# connectors.net
KiCad netlist of a schematic drawn in Altium Designer
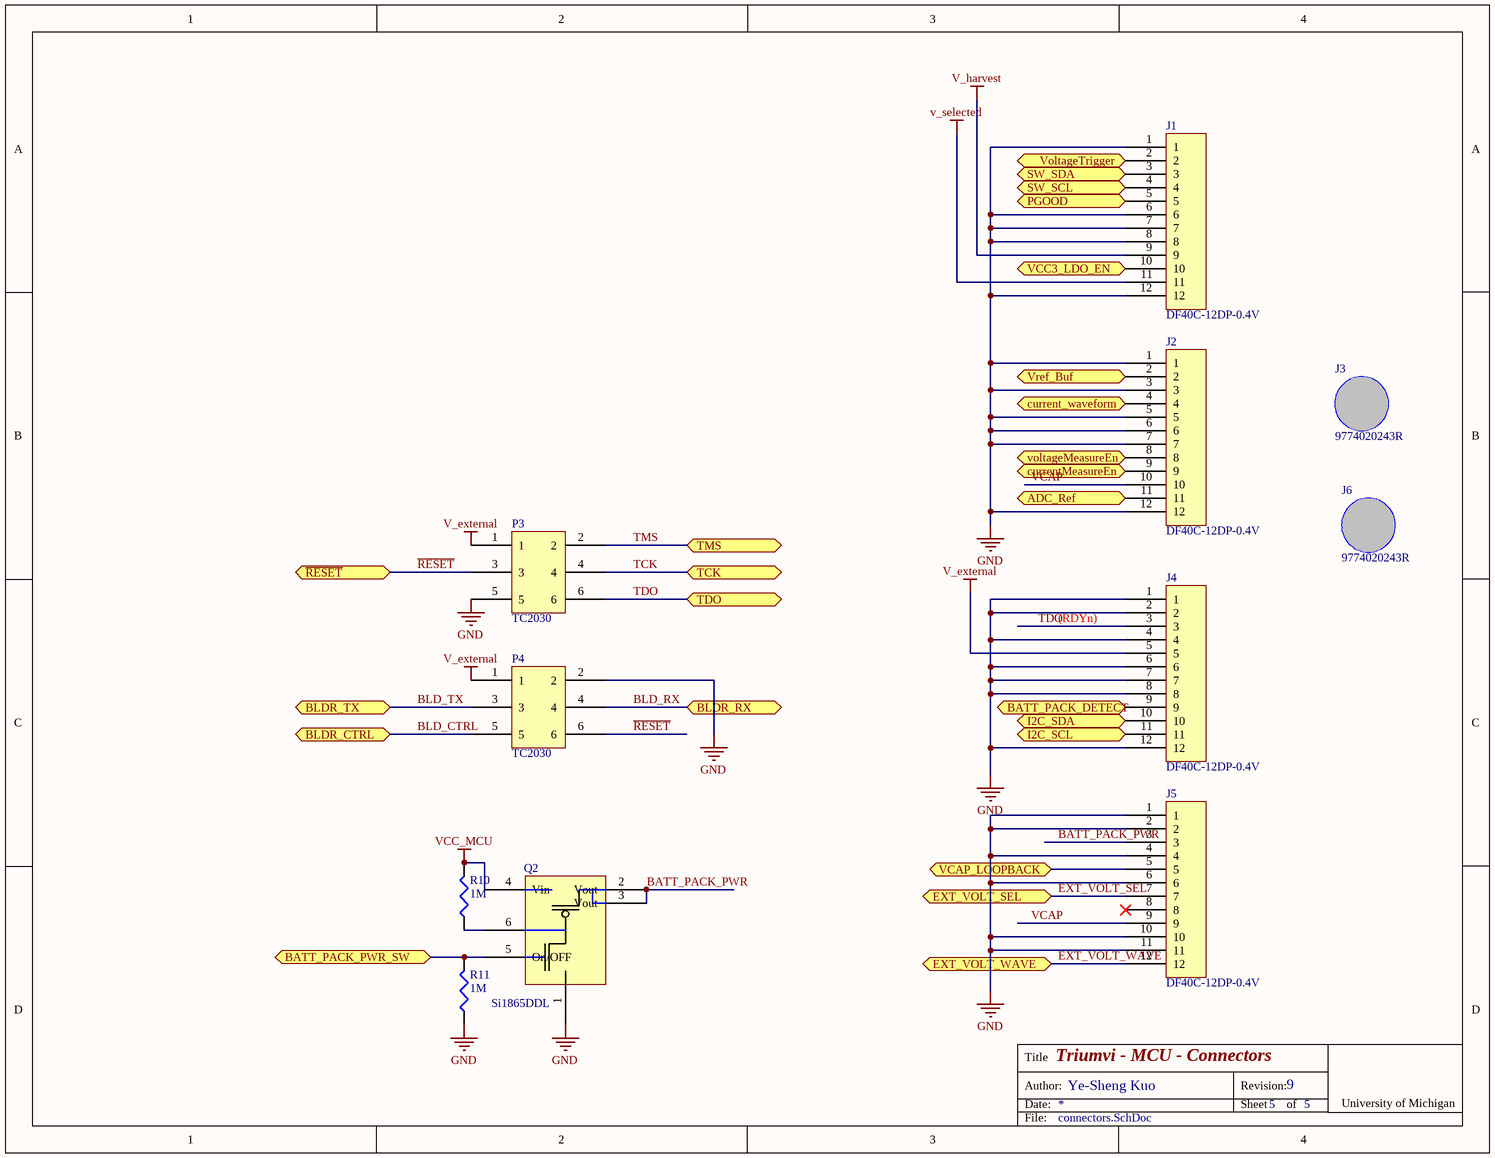
[diagram p0: connectors.SchDoc]

(export (version "E")
  (design (tool "Eeschema 10.0.6"))
  (components
    (comp (ref "J1")
      (value "DF40C-12DP-0.4V")
      (footprint "DF40C-12DP-0.4V")
      (description "Hirose BM20 Series, 0.4mm pitch, 12 pos, header")
      (libsource (lib "connectors") (part "DF40C-12DP-0.4V"))
    )
    (comp (ref "J2")
      (value "DF40C-12DP-0.4V")
      (footprint "DF40C-12DP-0.4V")
      (description "Hirose BM20 Series, 0.4mm pitch, 12 pos, header")
      (libsource (lib "connectors") (part "DF40C-12DP-0.4V"))
    )
    (comp (ref "J3")
      (value "9774020243R")
      (footprint "9774020243R")
      (description "2 mm stack height, m2 standoff")
      (libsource (lib "connectors") (part "9774020243R"))
    )
    (comp (ref "J4")
      (value "DF40C-12DP-0.4V")
      (footprint "DF40C-12DP-0.4V")
      (description "Hirose BM20 Series, 0.4mm pitch, 12 pos, header")
      (libsource (lib "connectors") (part "DF40C-12DP-0.4V"))
    )
    (comp (ref "J5")
      (value "DF40C-12DP-0.4V")
      (footprint "DF40C-12DP-0.4V")
      (description "Hirose BM20 Series, 0.4mm pitch, 12 pos, header")
      (libsource (lib "connectors") (part "DF40C-12DP-0.4V"))
    )
    (comp (ref "J6")
      (value "9774020243R")
      (footprint "9774020243R")
      (description "2 mm stack height, m2 standoff")
      (libsource (lib "connectors") (part "9774020243R"))
    )
    (comp (ref "P3")
      (value "TC2030")
      (footprint "TC2030-IDC-NLFP")
      (description "TC2030-MCP-NL")
      (libsource (lib "connectors") (part "TC2030"))
    )
    (comp (ref "P4")
      (value "TC2030")
      (footprint "TC2030-IDC-NLFP")
      (description "TC2030-MCP-NL")
      (libsource (lib "connectors") (part "TC2030"))
    )
    (comp (ref "Q2")
      (value "Si1865DDL")
      (footprint "SC70-6")
      (description "Load Switch with Level-Shift")
      (libsource (lib "power_switch") (part "Si1865DDL"))
    )
    (comp (ref "R10")
      (value "1M")
      (footprint "0402")
      (description "Chip resistor, 1M, 0402 package")
      (fields (field (name "TOLERANCE") "1%") (field (name "POWER") "1/16 W"))
      (libsource (lib "rlc") (part "R_1M_0402"))
    )
    (comp (ref "R11")
      (value "1M")
      (footprint "0402")
      (description "Chip resistor, 1M, 0402 package")
      (fields (field (name "TOLERANCE") "1%") (field (name "POWER") "1/16 W"))
      (libsource (lib "rlc") (part "R_1M_0402"))
    )
  )
  (nets
    (net (code "1") (name "/ADC_Ref") (class "Default")
      (node (ref "J2") (pin "11") (pinfunction "11_11") (pintype "passive"))
    )
    (net (code "2") (name "/BATT_PACK_DETECT") (class "Default")
      (node (ref "J4") (pin "9") (pinfunction "9_9") (pintype "passive"))
    )
    (net (code "3") (name "/BATT_PACK_PWR") (class "Default")
      (node (ref "J5") (pin "3") (pinfunction "3_3") (pintype "passive"))
      (node (ref "Q2") (pin "2") (pinfunction "Vout_2") (pintype "passive"))
      (node (ref "Q2") (pin "3") (pinfunction "Vout_3") (pintype "passive"))
    )
    (net (code "4") (name "/BATT_PACK_PWR_SW") (class "Default")
      (node (ref "Q2") (pin "5") (pinfunction "On/OFF_5") (pintype "passive"))
      (node (ref "R11") (pin "1") (pintype "passive"))
    )
    (net (code "5") (name "/BLD_CTRL") (class "Default")
      (node (ref "P4") (pin "5") (pinfunction "5_5") (pintype "passive"))
    )
    (net (code "6") (name "/BLD_RX") (class "Default")
      (node (ref "P4") (pin "4") (pinfunction "4_4") (pintype "passive"))
    )
    (net (code "7") (name "/BLD_TX") (class "Default")
      (node (ref "P4") (pin "3") (pinfunction "3_3") (pintype "passive"))
    )
    (net (code "8") (name "/EXT_VOLT_SEL") (class "Default")
      (node (ref "J5") (pin "7") (pinfunction "7_7") (pintype "passive"))
    )
    (net (code "9") (name "/EXT_VOLT_WAVE") (class "Default")
      (node (ref "J5") (pin "12") (pinfunction "12_12") (pintype "passive"))
    )
    (net (code "10") (name "/I2C_SCL") (class "Default")
      (node (ref "J4") (pin "11") (pinfunction "11_11") (pintype "passive"))
    )
    (net (code "11") (name "/I2C_SDA") (class "Default")
      (node (ref "J4") (pin "10") (pinfunction "10_10") (pintype "passive"))
    )
    (net (code "12") (name "/PGOOD") (class "Default")
      (node (ref "J1") (pin "5") (pinfunction "5_5") (pintype "passive"))
    )
    (net (code "13") (name "/SW_SCL") (class "Default")
      (node (ref "J1") (pin "4") (pinfunction "4_4") (pintype "passive"))
    )
    (net (code "14") (name "/SW_SDA") (class "Default")
      (node (ref "J1") (pin "3") (pinfunction "3_3") (pintype "passive"))
    )
    (net (code "15") (name "/TCK") (class "Default")
      (node (ref "P3") (pin "4") (pinfunction "4_4") (pintype "passive"))
    )
    (net (code "16") (name "/TDO") (class "Default")
      (node (ref "J4") (pin "3") (pinfunction "3_3") (pintype "passive"))
      (node (ref "P3") (pin "6") (pinfunction "6_6") (pintype "passive"))
    )
    (net (code "17") (name "/TMS") (class "Default")
      (node (ref "P3") (pin "2") (pinfunction "2_2") (pintype "passive"))
    )
    (net (code "18") (name "/VCAP") (class "Default")
      (node (ref "J2") (pin "10") (pinfunction "10_10") (pintype "passive"))
      (node (ref "J5") (pin "9") (pinfunction "9_9") (pintype "passive"))
    )
    (net (code "19") (name "/VCAP_LOOPBACK") (class "Default")
      (node (ref "J5") (pin "5") (pinfunction "5_5") (pintype "passive"))
    )
    (net (code "20") (name "/VCC3_LDO_EN") (class "Default")
      (node (ref "J1") (pin "10") (pinfunction "10_10") (pintype "passive"))
    )
    (net (code "21") (name "/VoltageTrigger") (class "Default")
      (node (ref "J1") (pin "2") (pinfunction "2_2") (pintype "passive"))
    )
    (net (code "22") (name "/Vref_Buf") (class "Default")
      (node (ref "J2") (pin "2") (pinfunction "2_2") (pintype "passive"))
    )
    (net (code "23") (name "/currentMeasureEn") (class "Default")
      (node (ref "J2") (pin "9") (pinfunction "9_9") (pintype "passive"))
    )
    (net (code "24") (name "/current_waveform") (class "Default")
      (node (ref "J2") (pin "4") (pinfunction "4_4") (pintype "passive"))
    )
    (net (code "25") (name "/voltageMeasureEn") (class "Default")
      (node (ref "J2") (pin "8") (pinfunction "8_8") (pintype "passive"))
    )
    (net (code "26") (name "/~{RESET}") (class "Default")
      (node (ref "P3") (pin "3") (pinfunction "3_3") (pintype "passive"))
      (node (ref "P4") (pin "6") (pinfunction "6_6") (pintype "passive"))
    )
    (net (code "27") (name "GND") (class "Default")
      (node (ref "J1") (pin "1") (pinfunction "1_1") (pintype "passive"))
      (node (ref "J1") (pin "12") (pinfunction "12_12") (pintype "passive"))
      (node (ref "J1") (pin "6") (pinfunction "6_6") (pintype "passive"))
      (node (ref "J1") (pin "7") (pinfunction "7_7") (pintype "passive"))
      (node (ref "J1") (pin "8") (pinfunction "8_8") (pintype "passive"))
      (node (ref "J2") (pin "1") (pinfunction "1_1") (pintype "passive"))
      (node (ref "J2") (pin "12") (pinfunction "12_12") (pintype "passive"))
      (node (ref "J2") (pin "3") (pinfunction "3_3") (pintype "passive"))
      (node (ref "J2") (pin "5") (pinfunction "5_5") (pintype "passive"))
      (node (ref "J2") (pin "6") (pinfunction "6_6") (pintype "passive"))
      (node (ref "J2") (pin "7") (pinfunction "7_7") (pintype "passive"))
      (node (ref "J4") (pin "1") (pinfunction "1_1") (pintype "passive"))
      (node (ref "J4") (pin "12") (pinfunction "12_12") (pintype "passive"))
      (node (ref "J4") (pin "2") (pinfunction "2_2") (pintype "passive"))
      (node (ref "J4") (pin "4") (pinfunction "4_4") (pintype "passive"))
      (node (ref "J4") (pin "6") (pinfunction "6_6") (pintype "passive"))
      (node (ref "J4") (pin "7") (pinfunction "7_7") (pintype "passive"))
      (node (ref "J4") (pin "8") (pinfunction "8_8") (pintype "passive"))
      (node (ref "J5") (pin "1") (pinfunction "1_1") (pintype "passive"))
      (node (ref "J5") (pin "10") (pinfunction "10_10") (pintype "passive"))
      (node (ref "J5") (pin "11") (pinfunction "11_11") (pintype "passive"))
      (node (ref "J5") (pin "2") (pinfunction "2_2") (pintype "passive"))
      (node (ref "J5") (pin "4") (pinfunction "4_4") (pintype "passive"))
      (node (ref "J5") (pin "6") (pinfunction "6_6") (pintype "passive"))
      (node (ref "P3") (pin "5") (pinfunction "5_5") (pintype "passive"))
      (node (ref "P4") (pin "2") (pinfunction "2_2") (pintype "passive"))
      (node (ref "Q2") (pin "1") (pinfunction "S1_1") (pintype "passive"))
      (node (ref "R11") (pin "2") (pintype "passive"))
    )
    (net (code "28") (name "Net-(Q2-D1)") (class "Default")
      (node (ref "Q2") (pin "6") (pinfunction "D1_6") (pintype "passive"))
      (node (ref "R10") (pin "2") (pintype "passive"))
    )
    (net (code "29") (name "VCC_MCU") (class "Default")
      (node (ref "Q2") (pin "4") (pinfunction "Vin_4") (pintype "passive"))
      (node (ref "R10") (pin "1") (pintype "passive"))
    )
    (net (code "30") (name "V_external") (class "Default")
      (node (ref "J4") (pin "5") (pinfunction "5_5") (pintype "passive"))
      (node (ref "P3") (pin "1") (pinfunction "1_1") (pintype "passive"))
      (node (ref "P4") (pin "1") (pinfunction "1_1") (pintype "passive"))
    )
    (net (code "31") (name "V_harvest") (class "Default")
      (node (ref "J1") (pin "9") (pinfunction "9_9") (pintype "passive"))
    )
    (net (code "32") (name "unconnected-(J5-Pad8)") (class "Default")
      (node (ref "J5") (pin "8") (pinfunction "8_8") (pintype "passive+no_connect"))
    )
    (net (code "33") (name "v_selected") (class "Default")
      (node (ref "J1") (pin "11") (pinfunction "11_11") (pintype "passive"))
    )
  )
)
